# MOTO.net
KiCad netlist of a schematic drawn in Altium Designer
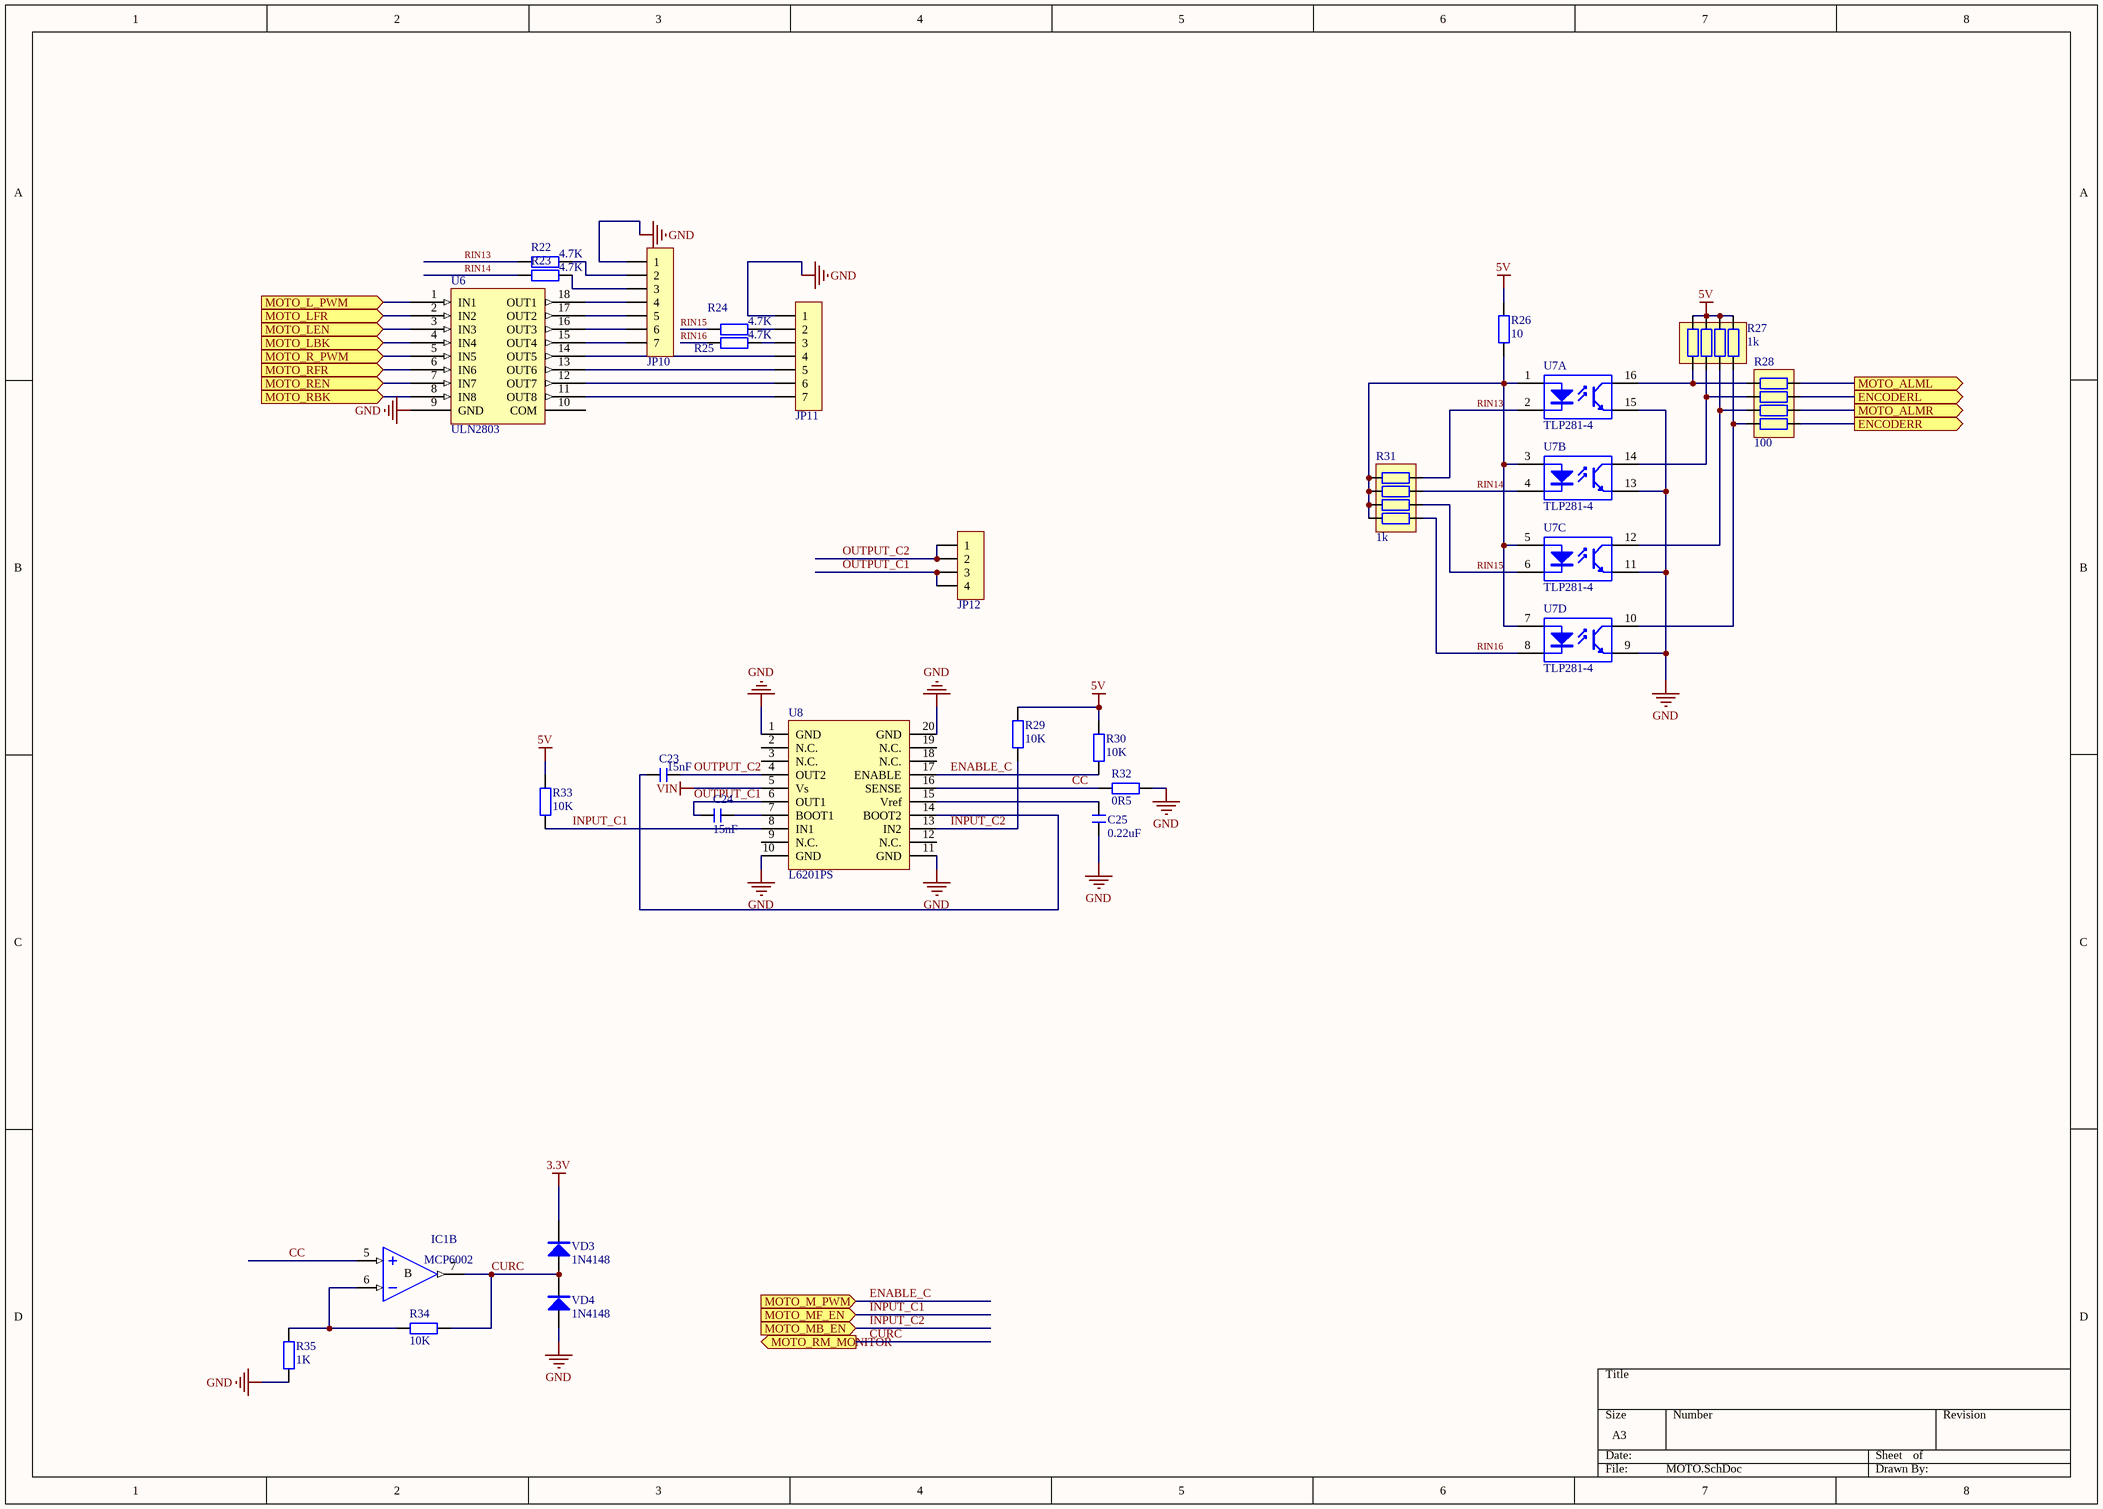
[diagram p0: MOTO.SchDoc]

(export (version "E")
  (design (tool "Eeschema 10.0.6"))
  (components
    (comp (ref "C23")
      (value "15nF")
      (footprint "C 0603_L")
      (description "无极性贴片电容")
      (fields (field (name "版权归属") "源创客"))
      (libsource (lib "3.1   - 电阻-电容-电感") (part "C"))
    )
    (comp (ref "C24")
      (value "15nF")
      (footprint "C 0603_L")
      (description "无极性贴片电容")
      (fields (field (name "版权归属") "源创客"))
      (libsource (lib "3.1   - 电阻-电容-电感") (part "C"))
    )
    (comp (ref "C25")
      (value "0.22uF")
      (footprint "C 0603_L")
      (description "无极性贴片电容")
      (fields (field (name "版权归属") "源创客"))
      (libsource (lib "3.1   - 电阻-电容-电感") (part "C"))
    )
    (comp (ref "IC1")
      (value "MCP6002")
      (footprint "SOP8_N")
      (description "双路运放")
      (fields (field (name "版权归属") "源创客"))
      (libsource (lib "IC芯片") (part "LM358"))
    )
    (comp (ref "JP10")
      (value "HDR-1X7")
      (footprint "XH2.54-WI-7P")
      (description "7P接插件")
      (fields (field (name "版权归属") "源创客"))
      (libsource (lib "4.5   - 接插件-脚距2.54") (part "Header 7"))
    )
    (comp (ref "JP11")
      (value "HDR-1X7")
      (footprint "XH2.54-WI-7P")
      (description "7P接插件")
      (fields (field (name "版权归属") "源创客"))
      (libsource (lib "4.5   - 接插件-脚距2.54") (part "Header 7"))
    )
    (comp (ref "JP12")
      (value "HDR-1X4")
      (footprint "XH2.54-WI-4P")
      (description "4P接插件")
      (fields (field (name "版权归属") "源创客"))
      (libsource (lib "4.5   - 接插件-脚距2.54") (part "Header 4"))
    )
    (comp (ref "R22")
      (value "4.7K")
      (footprint "R 0603_L")
      (description "贴片电阻")
      (fields (field (name "版权归属") "源创客"))
      (libsource (lib "3.1   - 电阻-电容-电感") (part "R"))
    )
    (comp (ref "R23")
      (value "4.7K")
      (footprint "R 0603_L")
      (description "贴片电阻")
      (fields (field (name "版权归属") "源创客"))
      (libsource (lib "3.1   - 电阻-电容-电感") (part "R"))
    )
    (comp (ref "R24")
      (value "4.7K")
      (footprint "R 0603_L")
      (description "贴片电阻")
      (fields (field (name "版权归属") "源创客"))
      (libsource (lib "3.1   - 电阻-电容-电感") (part "R"))
    )
    (comp (ref "R25")
      (value "4.7K")
      (footprint "R 0603_L")
      (description "贴片电阻")
      (fields (field (name "版权归属") "源创客"))
      (libsource (lib "3.1   - 电阻-电容-电感") (part "R"))
    )
    (comp (ref "R26")
      (value "10")
      (footprint "R 0603_L")
      (description "贴片电阻")
      (fields (field (name "版权归属") "源创客"))
      (libsource (lib "3.1   - 电阻-电容-电感") (part "R"))
    )
    (comp (ref "R27")
      (value "1k")
      (footprint "RCA-8P4R-0603")
      (description "贴片网络排阻")
      (fields (field (name "版权归属") "源创客"))
      (libsource (lib "电阻-电容-电感") (part "R-8P4R"))
    )
    (comp (ref "R28")
      (value "100")
      (footprint "RCA-8P4R-0603")
      (description "贴片网络排阻")
      (fields (field (name "版权归属") "源创客"))
      (libsource (lib "") (part "R-8P4R_2"))
    )
    (comp (ref "R29")
      (value "10K")
      (footprint "R 0603_L")
      (description "贴片电阻")
      (fields (field (name "版权归属") "源创客"))
      (libsource (lib "3.1   - 电阻-电容-电感") (part "R"))
    )
    (comp (ref "R30")
      (value "10K")
      (footprint "R 0603_L")
      (description "贴片电阻")
      (fields (field (name "版权归属") "源创客"))
      (libsource (lib "3.1   - 电阻-电容-电感") (part "R"))
    )
    (comp (ref "R31")
      (value "1k")
      (footprint "RCA-8P4R-0603")
      (description "贴片网络排阻")
      (fields (field (name "版权归属") "源创客"))
      (libsource (lib "") (part "R-8P4R_1"))
    )
    (comp (ref "R32")
      (value "0R5")
      (footprint "RS 3W-V7")
      (description "直插色环电阻")
      (fields (field (name "版权归属") "源创客"))
      (libsource (lib "电阻-电容-电感") (part "R-CRR"))
    )
    (comp (ref "R33")
      (value "10K")
      (footprint "R 0603_L")
      (description "贴片电阻")
      (fields (field (name "版权归属") "源创客"))
      (libsource (lib "3.1   - 电阻-电容-电感") (part "R"))
    )
    (comp (ref "R34")
      (value "10K")
      (footprint "R 0603_L")
      (description "贴片电阻")
      (fields (field (name "版权归属") "源创客"))
      (libsource (lib "3.1   - 电阻-电容-电感") (part "R"))
    )
    (comp (ref "R35")
      (value "1K")
      (footprint "R 0603_L")
      (description "贴片电阻")
      (fields (field (name "版权归属") "源创客"))
      (libsource (lib "3.1   - 电阻-电容-电感") (part "R"))
    )
    (comp (ref "U6") (value "ULN2803") (footprint "SO-G18") (libsource (lib "总图") (part "ULN2803")))
    (comp (ref "U7") (value "TLP281-4") (footprint "SOP16N_N") (libsource (lib "自编原件库") (part "TLP281-4")))
    (comp (ref "U8")
      (value "L6201PS")
      (footprint "SO_PowerSO20")
      (description "电机驱动H桥")
      (libsource (lib "元件库合集") (part "L6201PS"))
    )
    (comp (ref "VD3")
      (value "1N4148")
      (footprint "SOD-323")
      (description "高速开关二极管")
      (fields (field (name "版权归属") "源创客"))
      (libsource (lib "二极管-整流桥") (part "1N4148"))
    )
    (comp (ref "VD4")
      (value "1N4148")
      (footprint "SOD-323")
      (description "高速开关二极管")
      (fields (field (name "版权归属") "源创客"))
      (libsource (lib "二极管-整流桥") (part "1N4148"))
    )
  )
  (nets
    (net (code "1") (name "/CC") (class "Default")
      (node (ref "IC1") (pin "5") (pinfunction "IN+_5") (pintype "input"))
      (node (ref "R32") (pin "1") (pinfunction "1_1") (pintype "passive"))
      (node (ref "U8") (pin "16") (pinfunction "SENSE_16") (pintype "passive"))
    )
    (net (code "2") (name "/CURC") (class "Default")
      (node (ref "IC1") (pin "7") (pinfunction "OUT_7") (pintype "output"))
      (node (ref "R34") (pin "2") (pinfunction "2_2") (pintype "passive"))
      (node (ref "VD3") (pin "1") (pinfunction "A_1") (pintype "passive"))
      (node (ref "VD4") (pin "2") (pinfunction "K_2") (pintype "passive"))
    )
    (net (code "3") (name "/ENABLE_C") (class "Default")
      (node (ref "R30") (pin "1") (pinfunction "1_1") (pintype "passive"))
      (node (ref "U8") (pin "17") (pinfunction "ENABLE_17") (pintype "passive"))
    )
    (net (code "4") (name "/ENCODERL") (class "Default")
      (node (ref "R28") (pin "2") (pinfunction "2_2") (pintype "passive"))
    )
    (net (code "5") (name "/ENCODERR") (class "Default")
      (node (ref "R28") (pin "4") (pinfunction "4_4") (pintype "passive"))
    )
    (net (code "6") (name "/INPUT_C1") (class "Default")
      (node (ref "R33") (pin "1") (pinfunction "1_1") (pintype "passive"))
      (node (ref "U8") (pin "8") (pinfunction "IN1_8") (pintype "passive"))
    )
    (net (code "7") (name "/INPUT_C2") (class "Default")
      (node (ref "R29") (pin "1") (pinfunction "1_1") (pintype "passive"))
      (node (ref "U8") (pin "13") (pinfunction "IN2_13") (pintype "passive"))
    )
    (net (code "8") (name "/MOTO_ALML") (class "Default")
      (node (ref "R28") (pin "1") (pinfunction "1_1") (pintype "passive"))
    )
    (net (code "9") (name "/MOTO_ALMR") (class "Default")
      (node (ref "R28") (pin "3") (pinfunction "3_3") (pintype "passive"))
    )
    (net (code "10") (name "/MOTO_LBK") (class "Default")
      (node (ref "U6") (pin "4") (pinfunction "IN4_4") (pintype "input"))
    )
    (net (code "11") (name "/MOTO_LEN") (class "Default")
      (node (ref "U6") (pin "3") (pinfunction "IN3_3") (pintype "input"))
    )
    (net (code "12") (name "/MOTO_LFR") (class "Default")
      (node (ref "U6") (pin "2") (pinfunction "IN2_2") (pintype "input"))
    )
    (net (code "13") (name "/MOTO_L_PWM") (class "Default")
      (node (ref "U6") (pin "1") (pinfunction "IN1_1") (pintype "input"))
    )
    (net (code "14") (name "/MOTO_RBK") (class "Default")
      (node (ref "U6") (pin "8") (pinfunction "IN8_8") (pintype "input"))
    )
    (net (code "15") (name "/MOTO_REN") (class "Default")
      (node (ref "U6") (pin "7") (pinfunction "IN7_7") (pintype "input"))
    )
    (net (code "16") (name "/MOTO_RFR") (class "Default")
      (node (ref "U6") (pin "6") (pinfunction "IN6_6") (pintype "input"))
    )
    (net (code "17") (name "/MOTO_R_PWM") (class "Default")
      (node (ref "U6") (pin "5") (pinfunction "IN5_5") (pintype "input"))
    )
    (net (code "18") (name "/OUTPUT_C1") (class "Default")
      (node (ref "C24") (pin "1") (pinfunction "1_1") (pintype "passive"))
      (node (ref "JP12") (pin "3") (pinfunction "3_3") (pintype "passive"))
      (node (ref "JP12") (pin "4") (pinfunction "4_4") (pintype "passive"))
      (node (ref "U8") (pin "6") (pinfunction "OUT1_6") (pintype "passive"))
    )
    (net (code "19") (name "/OUTPUT_C2") (class "Default")
      (node (ref "C23") (pin "2") (pinfunction "2_2") (pintype "passive"))
      (node (ref "JP12") (pin "1") (pinfunction "1_1") (pintype "passive"))
      (node (ref "JP12") (pin "2") (pinfunction "2_2") (pintype "passive"))
      (node (ref "U8") (pin "4") (pinfunction "OUT2_4") (pintype "passive"))
    )
    (net (code "20") (name "/RIN13") (class "Default")
      (node (ref "R22") (pin "2") (pinfunction "2_2") (pintype "passive"))
      (node (ref "R31") (pin "8") (pinfunction "8_8") (pintype "passive"))
      (node (ref "U7") (pin "2") (pinfunction "2_2") (pintype "passive"))
    )
    (net (code "21") (name "/RIN14") (class "Default")
      (node (ref "R23") (pin "2") (pinfunction "2_2") (pintype "passive"))
      (node (ref "R31") (pin "7") (pinfunction "7_7") (pintype "passive"))
      (node (ref "U7") (pin "4") (pinfunction "4_4") (pintype "passive"))
    )
    (net (code "22") (name "/RIN15") (class "Default")
      (node (ref "R24") (pin "2") (pinfunction "2_2") (pintype "passive"))
      (node (ref "R31") (pin "6") (pinfunction "6_6") (pintype "passive"))
      (node (ref "U7") (pin "6") (pinfunction "6_6") (pintype "passive"))
    )
    (net (code "23") (name "/RIN16") (class "Default")
      (node (ref "R25") (pin "2") (pinfunction "2_2") (pintype "passive"))
      (node (ref "R31") (pin "5") (pinfunction "5_5") (pintype "passive"))
      (node (ref "U7") (pin "8") (pinfunction "8_8") (pintype "passive"))
    )
    (net (code "24") (name "3.3V") (class "Default")
      (node (ref "VD3") (pin "2") (pinfunction "K_2") (pintype "passive"))
    )
    (net (code "25") (name "5V") (class "Default")
      (node (ref "R26") (pin "1") (pinfunction "1_1") (pintype "passive"))
      (node (ref "R27") (pin "5") (pinfunction "5_5") (pintype "passive"))
      (node (ref "R27") (pin "6") (pinfunction "6_6") (pintype "passive"))
      (node (ref "R27") (pin "7") (pinfunction "7_7") (pintype "passive"))
      (node (ref "R27") (pin "8") (pinfunction "8_8") (pintype "passive"))
      (node (ref "R29") (pin "2") (pinfunction "2_2") (pintype "passive"))
      (node (ref "R30") (pin "2") (pinfunction "2_2") (pintype "passive"))
      (node (ref "R33") (pin "2") (pinfunction "2_2") (pintype "passive"))
    )
    (net (code "26") (name "GND") (class "Default")
      (node (ref "C25") (pin "1") (pinfunction "1_1") (pintype "passive"))
      (node (ref "JP10") (pin "1") (pinfunction "1_1") (pintype "passive"))
      (node (ref "JP11") (pin "1") (pinfunction "1_1") (pintype "passive"))
      (node (ref "R32") (pin "2") (pinfunction "2_2") (pintype "passive"))
      (node (ref "R35") (pin "1") (pinfunction "1_1") (pintype "passive"))
      (node (ref "U6") (pin "9") (pinfunction "GND_9") (pintype "passive"))
      (node (ref "U7") (pin "11") (pinfunction "11_11") (pintype "passive"))
      (node (ref "U7") (pin "13") (pinfunction "13_13") (pintype "passive"))
      (node (ref "U7") (pin "15") (pinfunction "15_15") (pintype "passive"))
      (node (ref "U7") (pin "9") (pinfunction "9_9") (pintype "passive"))
      (node (ref "U8") (pin "1") (pinfunction "GND_1") (pintype "passive"))
      (node (ref "U8") (pin "10") (pinfunction "GND_10") (pintype "passive"))
      (node (ref "U8") (pin "11") (pinfunction "GND_11") (pintype "passive"))
      (node (ref "U8") (pin "20") (pinfunction "GND_20") (pintype "passive"))
      (node (ref "VD4") (pin "1") (pinfunction "A_1") (pintype "passive"))
    )
    (net (code "27") (name "Net-(IC1B-IN-)") (class "Default")
      (node (ref "IC1") (pin "6") (pinfunction "IN-_6") (pintype "input"))
      (node (ref "R34") (pin "1") (pinfunction "1_1") (pintype "passive"))
      (node (ref "R35") (pin "2") (pinfunction "2_2") (pintype "passive"))
    )
    (net (code "28") (name "Net-(JP10-Pad2)") (class "Default")
      (node (ref "JP10") (pin "2") (pinfunction "2_2") (pintype "passive"))
      (node (ref "R22") (pin "1") (pinfunction "1_1") (pintype "passive"))
    )
    (net (code "29") (name "Net-(JP10-Pad3)") (class "Default")
      (node (ref "JP10") (pin "3") (pinfunction "3_3") (pintype "passive"))
      (node (ref "R23") (pin "1") (pinfunction "1_1") (pintype "passive"))
    )
    (net (code "30") (name "Net-(JP11-Pad2)") (class "Default")
      (node (ref "JP11") (pin "2") (pinfunction "2_2") (pintype "passive"))
      (node (ref "R24") (pin "1") (pinfunction "1_1") (pintype "passive"))
    )
    (net (code "31") (name "Net-(JP11-Pad3)") (class "Default")
      (node (ref "JP11") (pin "3") (pinfunction "3_3") (pintype "passive"))
      (node (ref "R25") (pin "1") (pinfunction "1_1") (pintype "passive"))
    )
    (net (code "32") (name "Net-(R26-Pad2)") (class "Default")
      (node (ref "R26") (pin "2") (pinfunction "2_2") (pintype "passive"))
      (node (ref "R31") (pin "1") (pinfunction "1_1") (pintype "passive"))
      (node (ref "R31") (pin "2") (pinfunction "2_2") (pintype "passive"))
      (node (ref "R31") (pin "3") (pinfunction "3_3") (pintype "passive"))
      (node (ref "R31") (pin "4") (pinfunction "4_4") (pintype "passive"))
      (node (ref "U7") (pin "1") (pinfunction "1_1") (pintype "passive"))
      (node (ref "U7") (pin "3") (pinfunction "3_3") (pintype "passive"))
      (node (ref "U7") (pin "5") (pinfunction "5_5") (pintype "passive"))
      (node (ref "U7") (pin "7") (pinfunction "7_7") (pintype "passive"))
    )
    (net (code "33") (name "Net-(R27-Pad1)") (class "Default")
      (node (ref "R27") (pin "1") (pinfunction "1_1") (pintype "passive"))
      (node (ref "R28") (pin "8") (pinfunction "8_8") (pintype "passive"))
      (node (ref "U7") (pin "16") (pinfunction "16_16") (pintype "passive"))
    )
    (net (code "34") (name "Net-(R27-Pad2)") (class "Default")
      (node (ref "R27") (pin "2") (pinfunction "2_2") (pintype "passive"))
      (node (ref "R28") (pin "7") (pinfunction "7_7") (pintype "passive"))
      (node (ref "U7") (pin "14") (pinfunction "14_14") (pintype "passive"))
    )
    (net (code "35") (name "Net-(R27-Pad3)") (class "Default")
      (node (ref "R27") (pin "3") (pinfunction "3_3") (pintype "passive"))
      (node (ref "R28") (pin "6") (pinfunction "6_6") (pintype "passive"))
      (node (ref "U7") (pin "12") (pinfunction "12_12") (pintype "passive"))
    )
    (net (code "36") (name "Net-(R27-Pad4)") (class "Default")
      (node (ref "R27") (pin "4") (pinfunction "4_4") (pintype "passive"))
      (node (ref "R28") (pin "5") (pinfunction "5_5") (pintype "passive"))
      (node (ref "U7") (pin "10") (pinfunction "10_10") (pintype "passive"))
    )
    (net (code "37") (name "Net-(U6-OUT1)") (class "Default")
      (node (ref "JP10") (pin "4") (pinfunction "4_4") (pintype "passive"))
      (node (ref "U6") (pin "18") (pinfunction "OUT1_18") (pintype "output"))
    )
    (net (code "38") (name "Net-(U6-OUT2)") (class "Default")
      (node (ref "JP10") (pin "5") (pinfunction "5_5") (pintype "passive"))
      (node (ref "U6") (pin "17") (pinfunction "OUT2_17") (pintype "output"))
    )
    (net (code "39") (name "Net-(U6-OUT3)") (class "Default")
      (node (ref "JP10") (pin "6") (pinfunction "6_6") (pintype "passive"))
      (node (ref "U6") (pin "16") (pinfunction "OUT3_16") (pintype "output"))
    )
    (net (code "40") (name "Net-(U6-OUT4)") (class "Default")
      (node (ref "JP10") (pin "7") (pinfunction "7_7") (pintype "passive"))
      (node (ref "U6") (pin "15") (pinfunction "OUT4_15") (pintype "output"))
    )
    (net (code "41") (name "Net-(U6-OUT5)") (class "Default")
      (node (ref "JP11") (pin "4") (pinfunction "4_4") (pintype "passive"))
      (node (ref "U6") (pin "14") (pinfunction "OUT5_14") (pintype "output"))
    )
    (net (code "42") (name "Net-(U6-OUT6)") (class "Default")
      (node (ref "JP11") (pin "5") (pinfunction "5_5") (pintype "passive"))
      (node (ref "U6") (pin "13") (pinfunction "OUT6_13") (pintype "output"))
    )
    (net (code "43") (name "Net-(U6-OUT7)") (class "Default")
      (node (ref "JP11") (pin "6") (pinfunction "6_6") (pintype "passive"))
      (node (ref "U6") (pin "12") (pinfunction "OUT7_12") (pintype "output"))
    )
    (net (code "44") (name "Net-(U6-OUT8)") (class "Default")
      (node (ref "JP11") (pin "7") (pinfunction "7_7") (pintype "passive"))
      (node (ref "U6") (pin "11") (pinfunction "OUT8_11") (pintype "output"))
    )
    (net (code "45") (name "Net-(U8-BOOT1)") (class "Default")
      (node (ref "C24") (pin "2") (pinfunction "2_2") (pintype "passive"))
      (node (ref "U8") (pin "7") (pinfunction "BOOT1_7") (pintype "passive"))
    )
    (net (code "46") (name "Net-(U8-BOOT2)") (class "Default")
      (node (ref "C23") (pin "1") (pinfunction "1_1") (pintype "passive"))
      (node (ref "U8") (pin "14") (pinfunction "BOOT2_14") (pintype "passive"))
    )
    (net (code "47") (name "Net-(U8-Vref)") (class "Default")
      (node (ref "C25") (pin "2") (pinfunction "2_2") (pintype "passive"))
      (node (ref "U8") (pin "15") (pinfunction "Vref_15") (pintype "passive"))
    )
    (net (code "48") (name "VIN") (class "Default")
      (node (ref "U8") (pin "5") (pinfunction "Vs_5") (pintype "passive"))
    )
    (net (code "49") (name "unconnected-(U6-COM-Pad10)") (class "Default")
      (node (ref "U6") (pin "10") (pinfunction "COM_10") (pintype "power_in"))
    )
    (net (code "50") (name "unconnected-(U8-N.C.-Pad2)") (class "Default")
      (node (ref "U8") (pin "2") (pinfunction "N.C._2") (pintype "passive"))
    )
    (net (code "51") (name "unconnected-(U8-N.C.-Pad3)") (class "Default")
      (node (ref "U8") (pin "3") (pinfunction "N.C._3") (pintype "passive"))
    )
    (net (code "52") (name "unconnected-(U8-N.C.-Pad9)") (class "Default")
      (node (ref "U8") (pin "9") (pinfunction "N.C._9") (pintype "passive"))
    )
    (net (code "53") (name "unconnected-(U8-N.C.-Pad12)") (class "Default")
      (node (ref "U8") (pin "12") (pinfunction "N.C._12") (pintype "passive"))
    )
    (net (code "54") (name "unconnected-(U8-N.C.-Pad18)") (class "Default")
      (node (ref "U8") (pin "18") (pinfunction "N.C._18") (pintype "passive"))
    )
    (net (code "55") (name "unconnected-(U8-N.C.-Pad19)") (class "Default")
      (node (ref "U8") (pin "19") (pinfunction "N.C._19") (pintype "passive"))
    )
  )
)
